# Switching_Scheme.net
KiCad netlist of a schematic drawn in Altium Designer
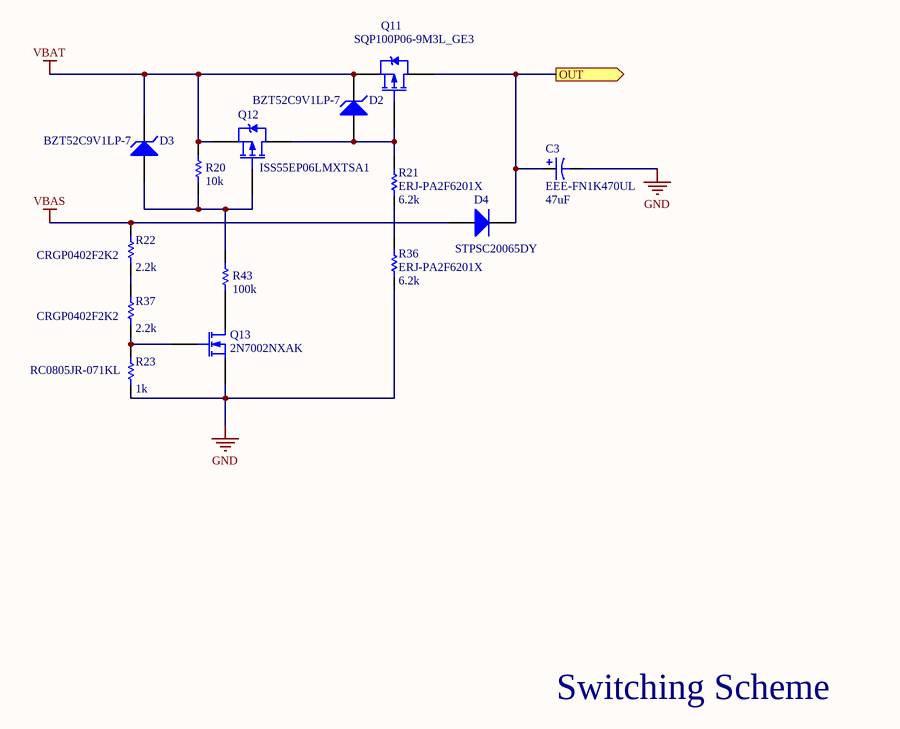
[diagram p0: Switching_Scheme.SchDoc]

(export (version "E")
  (design (tool "Eeschema 10.0.6"))
  (components
    (comp (ref "C3")
      (value "EEE-FN1K470UL")
      (footprint "CAPAE1030X1450N")
      (description "80VDC 47uF 20% 8x10.2mm AEC-Q200")
      (fields (field (name "MFG") "Panasonic") (field (name "ALTIUM_VALUE") "47uF"))
      (libsource (lib "Miscellaneous Devices") (part "Cap Pol1"))
    )
    (comp (ref "D2")
      (value "BZT52C9V1LP-7")
      (footprint "0402")
      (description "Zener Diode 9.1V 250mW ±6% Surface Mount X1-DFN1006-2")
      (fields (field (name "MFG") "Diodes Incorporated"))
      (libsource (lib "Miscellaneous Devices") (part "D Zener"))
    )
    (comp (ref "D3")
      (value "BZT52C9V1LP-7")
      (footprint "0402")
      (description "Zener Diode 9.1V 250mW ±6% Surface Mount X1-DFN1006-2")
      (fields (field (name "MFG") "Diodes Incorporated"))
      (libsource (lib "Miscellaneous Devices") (part "D Zener"))
    )
    (comp (ref "D4")
      (value "STPSC20065DY")
      (footprint "TO-220AC")
      (description "Diode Silicon Carbide Schottky 650V 20A Through Hole TO-220AC")
      (fields (field (name "MFG") "STMicroelectronics"))
      (libsource (lib "Miscellaneous Devices") (part "Diode"))
    )
    (comp (ref "Q11")
      (value "SQP100P06-9M3L_GE3")
      (footprint "TO-220AB")
      (description "P-Channel 60V 100A (Tc) 187W (Tc) Through Hole TO-220AB")
      (fields (field (name "PUBLISHER") "Vishay Siliconix"))
      (libsource (lib "Miscellaneous Devices") (part "PMOS-2"))
    )
    (comp (ref "Q12")
      (value "ISS55EP06LMXTSA1")
      (footprint "SOT23_L")
      (description "P-Channel 60V 180mA (Ta) 400mW (Ta) Surface Mount PG-SOT23-3-5")
      (fields (field (name "MFG") "Infineon Technologies") (field (name "PUBLISHER") "ISS55EP06LMXTSA1"))
      (libsource (lib "Miscellaneous Devices") (part "PMOS-2"))
    )
    (comp (ref "Q13")
      (value "2N7002NXAK")
      (footprint "SOT23_L")
      (description "N-Channel 60V 190mA (Ta), 300mA (Tc) 265mW (Ta), 1.33W (Tc) Surface Mount TO-236AB")
      (fields (field (name "MFG") "Nexperia USA"))
      (libsource (lib "Miscellaneous Devices") (part "MOSFET-N"))
    )
    (comp (ref "R20")
      (value "10k")
      (footprint "0402")
      (description "10 kOhms ±1% 0.063W, 1/16W Chip Resistor 0402 (1005 Metric) Thick Film")
      (fields (field (name "MANUFACTURER") "Yageo") (field (name "Comment") "RC0402FR-0710KL"))
      (libsource (lib "Miscellaneous Devices") (part "Res1"))
    )
    (comp (ref "R21")
      (value "ERJ-PA2F6201X")
      (footprint "0402")
      (description "±1% 0.2W, 1/5W Chip Resistor 0402 (1005 Metric) Automotive AEC-Q200, Pulse Withstanding Thick Film")
      (fields
        (field (name "MANUFACTURER") "Panasonic Electronic Components")
        (field (name "ALTIUM_VALUE") "6.2k")
      )
      (libsource (lib "Miscellaneous Devices") (part "Res1"))
    )
    (comp (ref "R22")
      (value "CRGP0402F2K2")
      (footprint "0402")
      (description "2.2 kOhms ±1% 0.125W, 1/8W Chip Resistor 0402 (1005 Metric) Pulse Withstanding Thick Film")
      (fields (field (name "ALTIUM_VALUE") "2.2k") (field (name "MFG") "TE Connectivity Passive Product"))
      (libsource (lib "Miscellaneous Devices") (part "Res1"))
    )
    (comp (ref "R23")
      (value "RC0805JR-071KL")
      (footprint "0402")
      (description "1 kOhms ±5% 0.125W, 1/8W Chip Resistor 0805 (2012 Metric)  Thick Film")
      (fields (field (name "MFG") "Yageo") (field (name "ALTIUM_VALUE") "1k"))
      (libsource (lib "Miscellaneous Devices") (part "Res1"))
    )
    (comp (ref "R36")
      (value "ERJ-PA2F6201X")
      (footprint "0402")
      (description "±1% 0.2W, 1/5W Chip Resistor 0402 (1005 Metric) Automotive AEC-Q200, Pulse Withstanding Thick Film")
      (fields
        (field (name "MANUFACTURER") "Panasonic Electronic Components")
        (field (name "ALTIUM_VALUE") "6.2k")
      )
      (libsource (lib "Miscellaneous Devices") (part "Res1"))
    )
    (comp (ref "R37")
      (value "CRGP0402F2K2")
      (footprint "0402")
      (description "2.2 kOhms ±1% 0.125W, 1/8W Chip Resistor 0402 (1005 Metric) Pulse Withstanding Thick Film")
      (fields (field (name "ALTIUM_VALUE") "2.2k") (field (name "MFG") "TE Connectivity Passive Product"))
      (libsource (lib "Miscellaneous Devices") (part "Res1"))
    )
    (comp (ref "R43")
      (value "100k")
      (footprint "0402")
      (description "10 kOhms ±1% 0.063W, 1/16W Chip Resistor 0402 (1005 Metric) Thick Film")
      (fields (field (name "MANUFACTURER") "Yageo") (field (name "Comment") "RC0402FR-0710KL"))
      (libsource (lib "Miscellaneous Devices") (part "Res1"))
    )
  )
  (nets
    (net (code "1") (name "/OUT") (class "Default")
      (node (ref "C3") (pin "1") (pinfunction "1_1") (pintype "passive"))
      (node (ref "D4") (pin "2") (pinfunction "K_2") (pintype "passive"))
      (node (ref "Q11") (pin "2") (pinfunction "D_2") (pintype "passive"))
    )
    (net (code "2") (name "GND") (class "Default")
      (node (ref "C3") (pin "2") (pinfunction "2_2") (pintype "passive"))
      (node (ref "Q13") (pin "3") (pinfunction "S_3") (pintype "passive"))
      (node (ref "R23") (pin "1") (pinfunction "1_1") (pintype "passive"))
      (node (ref "R36") (pin "2") (pinfunction "2_2") (pintype "passive"))
    )
    (net (code "3") (name "Net-(D2-A)") (class "Default")
      (node (ref "D2") (pin "1") (pinfunction "A_1") (pintype "passive"))
      (node (ref "Q11") (pin "1") (pinfunction "G_1") (pintype "passive"))
      (node (ref "Q12") (pin "2") (pinfunction "D_2") (pintype "passive"))
      (node (ref "R21") (pin "1") (pinfunction "1_1") (pintype "passive"))
    )
    (net (code "4") (name "Net-(D3-A)") (class "Default")
      (node (ref "D3") (pin "1") (pinfunction "A_1") (pintype "passive"))
      (node (ref "Q12") (pin "1") (pinfunction "G_1") (pintype "passive"))
      (node (ref "R20") (pin "1") (pinfunction "1_1") (pintype "passive"))
      (node (ref "R43") (pin "2") (pinfunction "2_2") (pintype "passive"))
    )
    (net (code "5") (name "Net-(Q13-D)") (class "Default")
      (node (ref "Q13") (pin "1") (pinfunction "D_1") (pintype "passive"))
      (node (ref "R43") (pin "1") (pinfunction "1_1") (pintype "passive"))
    )
    (net (code "6") (name "Net-(Q13-G)") (class "Default")
      (node (ref "Q13") (pin "2") (pinfunction "G_2") (pintype "passive"))
      (node (ref "R23") (pin "2") (pinfunction "2_2") (pintype "passive"))
      (node (ref "R37") (pin "1") (pinfunction "1_1") (pintype "passive"))
    )
    (net (code "7") (name "Net-(R21-Pad2)") (class "Default")
      (node (ref "R21") (pin "2") (pinfunction "2_2") (pintype "passive"))
      (node (ref "R36") (pin "1") (pinfunction "1_1") (pintype "passive"))
    )
    (net (code "8") (name "Net-(R22-Pad1)") (class "Default")
      (node (ref "R22") (pin "1") (pinfunction "1_1") (pintype "passive"))
      (node (ref "R37") (pin "2") (pinfunction "2_2") (pintype "passive"))
    )
    (net (code "9") (name "VBAS") (class "Default")
      (node (ref "D4") (pin "1") (pinfunction "A_1") (pintype "passive"))
      (node (ref "R22") (pin "2") (pinfunction "2_2") (pintype "passive"))
    )
    (net (code "10") (name "VBAT") (class "Default")
      (node (ref "D2") (pin "2") (pinfunction "K_2") (pintype "passive"))
      (node (ref "D3") (pin "2") (pinfunction "K_2") (pintype "passive"))
      (node (ref "Q11") (pin "3") (pinfunction "S_3") (pintype "passive"))
      (node (ref "Q12") (pin "3") (pinfunction "S_3") (pintype "passive"))
      (node (ref "R20") (pin "2") (pinfunction "2_2") (pintype "passive"))
    )
  )
)
